# Diff2SE.net
KiCad netlist of a schematic drawn in Altium Designer
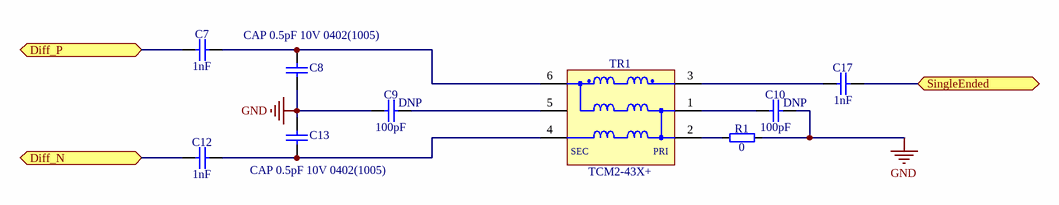
[diagram p0: Diff2SE.SchDoc]

(export (version "E")
  (design (tool "Eeschema 10.0.6"))
  (components
    (comp (ref "C7")
      (value "1nF")
      (footprint "CAPC1005X55N")
      (description "Non-polarised capacitor")
      (fields
        (field (name "PART NUMBER") "CC0402_1NF_50V_10%_X7R")
        (field (name "VOLTAGE") "50V")
        (field (name "AUTHOR") "CERN DEM JLC")
      )
      (libsource (lib "Capacitors") (part "Capacitor - non polarized"))
    )
    (comp (ref "C8")
      (value "CAP 0.5pF 10V 0402(1005)")
      (footprint "CAPC0402(1005)60_M")
      (description "CAP 0.5pF 10V ±0.1pF 0402 (1005 Metric) Thickness 0.6mm SMD")
      (fields (field (name "TOLERANCE") "Â±0.1pF"))
      (libsource (lib "Altium Content Vault") (part "CAP"))
    )
    (comp (ref "C9")
      (value "100pF")
      (footprint "CAPC1005X55N")
      (description "Non-polarised capacitor")
      (fields
        (field (name "PART NUMBER") "CC0402_100PF_50V_5%_C0G")
        (field (name "VOLTAGE") "50V")
        (field (name "MOUNTED") "DNP")
        (field (name "AUTHOR") "CERN DEM JLC")
      )
      (libsource (lib "Capacitors") (part "Capacitor - non polarized"))
    )
    (comp (ref "C10")
      (value "100pF")
      (footprint "CAPC1005X55N")
      (description "Non-polarised capacitor")
      (fields
        (field (name "PART NUMBER") "CC0402_100PF_50V_5%_C0G")
        (field (name "VOLTAGE") "50V")
        (field (name "MOUNTED") "DNP")
        (field (name "AUTHOR") "CERN DEM JLC")
      )
      (libsource (lib "Capacitors") (part "Capacitor - non polarized"))
    )
    (comp (ref "C12")
      (value "1nF")
      (footprint "CAPC1005X55N")
      (description "Non-polarised capacitor")
      (fields
        (field (name "PART NUMBER") "CC0402_1NF_50V_10%_X7R")
        (field (name "VOLTAGE") "50V")
        (field (name "AUTHOR") "CERN DEM JLC")
      )
      (libsource (lib "Capacitors") (part "Capacitor - non polarized"))
    )
    (comp (ref "C13")
      (value "CAP 0.5pF 10V 0402(1005)")
      (footprint "CAPC0402(1005)60_M")
      (description "CAP 0.5pF 10V ±0.1pF 0402 (1005 Metric) Thickness 0.6mm SMD")
      (fields (field (name "TOLERANCE") "Â±0.1pF"))
      (libsource (lib "Altium Content Vault") (part "CAP"))
    )
    (comp (ref "C17")
      (value "1nF")
      (footprint "CAPC1005X55N")
      (description "Non-polarised capacitor")
      (fields
        (field (name "PART NUMBER") "CC0402_1NF_50V_10%_X7R")
        (field (name "VOLTAGE") "50V")
        (field (name "AUTHOR") "CERN DEM JLC")
      )
      (libsource (lib "Capacitors") (part "Capacitor - non polarized"))
    )
    (comp (ref "R1")
      (value "0")
      (footprint "RESC1005X40N")
      (description "Resistor")
      (fields
        (field (name "PART NUMBER") "R0402_0R_JUMPER")
        (field (name "MANUFACTURER") "GENERIC")
        (field (name "AUTHOR") "CERN DEM JLC")
      )
      (libsource (lib "Resistors") (part "Resistor"))
    )
    (comp (ref "TR1")
      (value "TCM2-43X+")
      (footprint "XFMR_MINI-CIRCUITS_DB1627")
      (description "50 OHMS 10 to 4000 MHz RF Transformer")
      (fields
        (field (name "PART NUMBER") "XFMR_MINI-CIRCUITS_TCM2-43X+")
        (field (name "POWER") "0.4W")
        (field (name "AUTHOR") "CERN DEM BC")
      )
      (libsource (lib "Inductors & Transformers") (part "XFMR_MINI-CIRCUITS_TCM2-43X"))
    )
  )
  (nets
    (net (code "1") (name "/Diff_N") (class "Default")
      (node (ref "C12") (pin "1") (pinfunction "1_1") (pintype "passive"))
    )
    (net (code "2") (name "/Diff_P") (class "Default")
      (node (ref "C7") (pin "1") (pinfunction "1_1") (pintype "passive"))
    )
    (net (code "3") (name "/SingleEnded") (class "Default")
      (node (ref "C17") (pin "2") (pinfunction "2_2") (pintype "passive"))
    )
    (net (code "4") (name "GND") (class "Default")
      (node (ref "C10") (pin "2") (pinfunction "2_2") (pintype "passive"))
      (node (ref "C13") (pin "2") (pinfunction "2_2") (pintype "passive"))
      (node (ref "C8") (pin "1") (pinfunction "1_1") (pintype "passive"))
      (node (ref "C9") (pin "1") (pinfunction "1_1") (pintype "passive"))
      (node (ref "R1") (pin "2") (pinfunction "2_2") (pintype "passive"))
    )
    (net (code "5") (name "Net-(C7-Pad2)") (class "Default")
      (node (ref "C7") (pin "2") (pinfunction "2_2") (pintype "passive"))
      (node (ref "C8") (pin "2") (pinfunction "2_2") (pintype "passive"))
      (node (ref "TR1") (pin "6") (pinfunction "S1_6") (pintype "passive"))
    )
    (net (code "6") (name "Net-(C10-Pad1)") (class "Default")
      (node (ref "C10") (pin "1") (pinfunction "1_1") (pintype "passive"))
      (node (ref "TR1") (pin "1") (pinfunction "P1_1") (pintype "passive"))
    )
    (net (code "7") (name "Net-(C12-Pad2)") (class "Default")
      (node (ref "C12") (pin "2") (pinfunction "2_2") (pintype "passive"))
      (node (ref "C13") (pin "1") (pinfunction "1_1") (pintype "passive"))
      (node (ref "TR1") (pin "4") (pinfunction "S1_4") (pintype "passive"))
    )
    (net (code "8") (name "Net-(C17-Pad1)") (class "Default")
      (node (ref "C17") (pin "1") (pinfunction "1_1") (pintype "passive"))
      (node (ref "TR1") (pin "3") (pinfunction "P1_3") (pintype "passive"))
    )
    (net (code "9") (name "Net-(R1-Pad1)") (class "Default")
      (node (ref "R1") (pin "1") (pinfunction "1_1") (pintype "passive"))
      (node (ref "TR1") (pin "2") (pinfunction "P1_2") (pintype "passive"))
    )
    (net (code "10") (name "Net-(TR1-NC)") (class "Default")
      (node (ref "C9") (pin "2") (pinfunction "2_2") (pintype "passive"))
      (node (ref "TR1") (pin "5") (pinfunction "NC_5") (pintype "passive"))
    )
  )
)
